# Motherboard.net
KiCad netlist of a schematic drawn in EAGLE
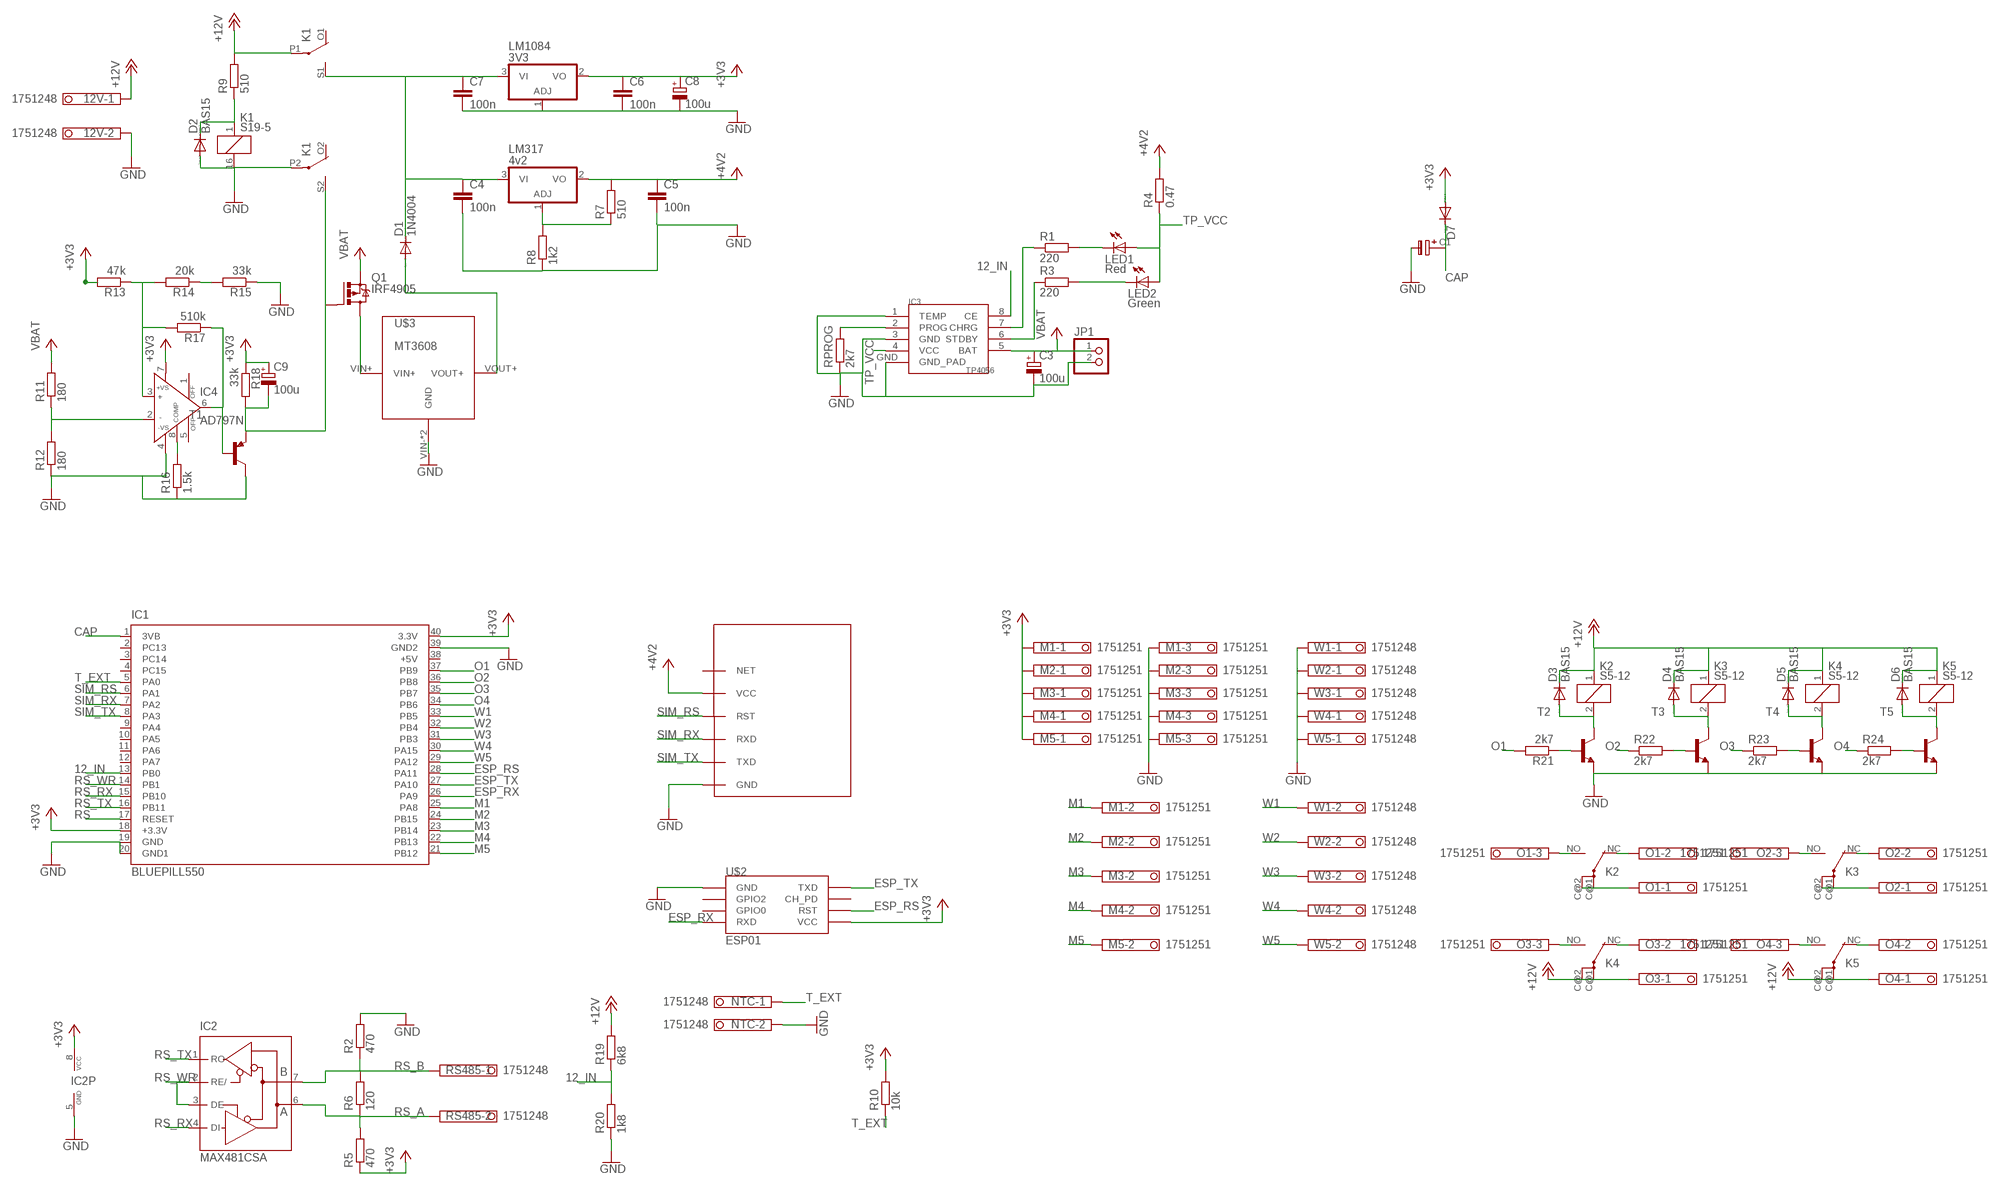
[diagram p0: schematic, sheet 1]

(export (version "E")
  (design (tool "Eeschema 10.0.6"))
  (components
    (comp (ref "12V")
      (value "1751248")
      (footprint "eagle-import:1751248")
      (libsource (lib "eagle-import") (part "1751248"))
    )
    (comp (ref "C1")
      (value "CAP-13,5")
      (footprint "eagle-import:PAC-G-1")
      (libsource (lib "eagle-import") (part "CAP-13,5"))
    )
    (comp (ref "C3")
      (value "100u")
      (footprint "eagle-import:E2,5-6E")
      (libsource (lib "eagle-import") (part "CPOL-EUE2,5-6E"))
    )
    (comp (ref "C4")
      (value "100n")
      (footprint "eagle-import:C2012")
      (libsource (lib "eagle-import") (part "C-EUC2012"))
    )
    (comp (ref "C5")
      (value "100n")
      (footprint "eagle-import:C2012")
      (libsource (lib "eagle-import") (part "C-EUC2012"))
    )
    (comp (ref "C6")
      (value "100n")
      (footprint "eagle-import:C2012")
      (libsource (lib "eagle-import") (part "C-EUC2012"))
    )
    (comp (ref "C7")
      (value "100n")
      (footprint "eagle-import:C2012")
      (libsource (lib "eagle-import") (part "C-EUC2012"))
    )
    (comp (ref "C8")
      (value "100u")
      (footprint "eagle-import:E2,5-6E")
      (libsource (lib "eagle-import") (part "CPOL-EUE2,5-6E"))
    )
    (comp (ref "C9")
      (value "100u")
      (footprint "eagle-import:E2,5-6E")
      (libsource (lib "eagle-import") (part "CPOL-EUE2,5-6E"))
    )
    (comp (ref "D1")
      (value "1N4004")
      (footprint "eagle-import:DO41-10")
      (libsource (lib "eagle-import") (part "1N4004"))
    )
    (comp (ref "D2")
      (value "BAS15")
      (footprint "eagle-import:DO34-7")
      (libsource (lib "eagle-import") (part "BAS15"))
    )
    (comp (ref "D3")
      (value "BAS15")
      (footprint "eagle-import:DO34-7")
      (libsource (lib "eagle-import") (part "BAS15"))
    )
    (comp (ref "D4")
      (value "BAS15")
      (footprint "eagle-import:DO34-7")
      (libsource (lib "eagle-import") (part "BAS15"))
    )
    (comp (ref "D5")
      (value "BAS15")
      (footprint "eagle-import:DO34-7")
      (libsource (lib "eagle-import") (part "BAS15"))
    )
    (comp (ref "D6")
      (value "BAS15")
      (footprint "eagle-import:DO34-7")
      (libsource (lib "eagle-import") (part "BAS15"))
    )
    (comp (ref "D7")
      (value "BAS15")
      (footprint "eagle-import:DO34-7")
      (libsource (lib "eagle-import") (part "BAS15"))
    )
    (comp (ref "IC1")
      (value "BLUEPILL550")
      (footprint "eagle-import:DIL40")
      (fields (field (name "MF") "BluePill"))
      (libsource (lib "eagle-import") (part "BLUEPILL550"))
    )
    (comp (ref "IC2")
      (value "MAX481CSA")
      (footprint "eagle-import:SO08")
      (fields (field (name "MF") "MAXIM"))
      (libsource (lib "eagle-import") (part "MAX481CSA"))
    )
    (comp (ref "IC3")
      (value "TP4056")
      (footprint "eagle-import:SOP-8")
      (libsource (lib "eagle-import") (part "TP4056"))
    )
    (comp (ref "IC4")
      (value "AD797N")
      (footprint "eagle-import:DIL08")
      (fields (field (name "MF") "ALTERA CORPORATION") (field (name "MPN") "AD797ANZ"))
      (libsource (lib "eagle-import") (part "AD797N"))
    )
    (comp (ref "JP1")
      (value "PINHD-1X2")
      (footprint "eagle-import:1X02")
      (libsource (lib "eagle-import") (part "PINHD-1X2"))
    )
    (comp (ref "K1")
      (value "S19-5")
      (footprint "eagle-import:351")
      (libsource (lib "eagle-import") (part "351"))
    )
    (comp (ref "K2")
      (value "S5-12")
      (footprint "eagle-import:HY")
      (fields (field (name "MF") "AROMAT/ MATSUSHITA") (field (name "MPN") "HY1-5V"))
      (libsource (lib "eagle-import") (part "HY1-5V"))
    )
    (comp (ref "K3")
      (value "S5-12")
      (footprint "eagle-import:HY")
      (fields (field (name "MF") "AROMAT/ MATSUSHITA") (field (name "MPN") "HY1-5V"))
      (libsource (lib "eagle-import") (part "HY1-5V"))
    )
    (comp (ref "K4")
      (value "S5-12")
      (footprint "eagle-import:HY")
      (fields (field (name "MF") "AROMAT/ MATSUSHITA") (field (name "MPN") "HY1-5V"))
      (libsource (lib "eagle-import") (part "HY1-5V"))
    )
    (comp (ref "K5")
      (value "S5-12")
      (footprint "eagle-import:HY")
      (fields (field (name "MF") "AROMAT/ MATSUSHITA") (field (name "MPN") "HY1-5V"))
      (libsource (lib "eagle-import") (part "HY1-5V"))
    )
    (comp (ref "LED1")
      (value "Red")
      (footprint "eagle-import:CHIP-LED0805")
      (libsource (lib "eagle-import") (part "LEDCHIP-LED0805"))
    )
    (comp (ref "LED2")
      (value "Green")
      (footprint "eagle-import:CHIP-LED0805")
      (libsource (lib "eagle-import") (part "LEDCHIP-LED0805"))
    )
    (comp (ref "LM317")
      (value "4v2")
      (footprint "eagle-import:TO220H")
      (libsource (lib "eagle-import") (part "317T"))
    )
    (comp (ref "LM1084")
      (value "3V3")
      (footprint "eagle-import:TO220H")
      (libsource (lib "eagle-import") (part "317T"))
    )
    (comp (ref "M1")
      (value "1751251")
      (footprint "eagle-import:1751251")
      (libsource (lib "eagle-import") (part "1751251"))
    )
    (comp (ref "M2")
      (value "1751251")
      (footprint "eagle-import:1751251")
      (libsource (lib "eagle-import") (part "1751251"))
    )
    (comp (ref "M3")
      (value "1751251")
      (footprint "eagle-import:1751251")
      (libsource (lib "eagle-import") (part "1751251"))
    )
    (comp (ref "M4")
      (value "1751251")
      (footprint "eagle-import:1751251")
      (libsource (lib "eagle-import") (part "1751251"))
    )
    (comp (ref "M5")
      (value "1751251")
      (footprint "eagle-import:1751251")
      (libsource (lib "eagle-import") (part "1751251"))
    )
    (comp (ref "NTC")
      (value "1751248")
      (footprint "eagle-import:1751248")
      (libsource (lib "eagle-import") (part "1751248"))
    )
    (comp (ref "O1")
      (value "1751251")
      (footprint "eagle-import:1751251")
      (libsource (lib "eagle-import") (part "1751251"))
    )
    (comp (ref "O2")
      (value "1751251")
      (footprint "eagle-import:1751251")
      (libsource (lib "eagle-import") (part "1751251"))
    )
    (comp (ref "O3")
      (value "1751251")
      (footprint "eagle-import:1751251")
      (libsource (lib "eagle-import") (part "1751251"))
    )
    (comp (ref "O4")
      (value "1751251")
      (footprint "eagle-import:1751251")
      (libsource (lib "eagle-import") (part "1751251"))
    )
    (comp (ref "Q1")
      (value "IRF4905")
      (footprint "eagle-import:TO220BH")
      (libsource (lib "eagle-import") (part "IRF4905"))
    )
    (comp (ref "R1")
      (value "220")
      (footprint "eagle-import:R0805")
      (libsource (lib "eagle-import") (part "resistor_R-EU_R0805"))
    )
    (comp (ref "R2")
      (value "470")
      (footprint "eagle-import:0204_5")
      (libsource (lib "eagle-import") (part "resistor_R-EU_0204/5"))
    )
    (comp (ref "R3")
      (value "220")
      (footprint "eagle-import:R0805")
      (libsource (lib "eagle-import") (part "resistor_R-EU_R0805"))
    )
    (comp (ref "R4")
      (value "0.47")
      (footprint "eagle-import:0207_12")
      (libsource (lib "eagle-import") (part "resistor_R-EU_0207/12"))
    )
    (comp (ref "R5")
      (value "470")
      (footprint "eagle-import:0204_5")
      (libsource (lib "eagle-import") (part "resistor_R-EU_0204/5"))
    )
    (comp (ref "R6")
      (value "120")
      (footprint "eagle-import:0204_7")
      (libsource (lib "eagle-import") (part "resistor_R-EU_0204/7"))
    )
    (comp (ref "R7")
      (value "510")
      (footprint "eagle-import:0204_7")
      (libsource (lib "eagle-import") (part "resistor_R-EU_0204/7"))
    )
    (comp (ref "R8")
      (value "1k2")
      (footprint "eagle-import:0204_7")
      (libsource (lib "eagle-import") (part "resistor_R-EU_0204/7"))
    )
    (comp (ref "R9")
      (value "510")
      (footprint "eagle-import:0204_7")
      (libsource (lib "eagle-import") (part "resistor_R-EU_0204/7"))
    )
    (comp (ref "R10")
      (value "10k")
      (footprint "eagle-import:0204_5")
      (libsource (lib "eagle-import") (part "R-EU_0204/5"))
    )
    (comp (ref "R11")
      (value "180")
      (footprint "eagle-import:0204_7")
      (libsource (lib "eagle-import") (part "resistor_R-EU_0204/7"))
    )
    (comp (ref "R12")
      (value "180")
      (footprint "eagle-import:0204_7")
      (libsource (lib "eagle-import") (part "resistor_R-EU_0204/7"))
    )
    (comp (ref "R13")
      (value "47k")
      (footprint "eagle-import:0204_7")
      (libsource (lib "eagle-import") (part "resistor_R-EU_0204/7"))
    )
    (comp (ref "R14")
      (value "20k")
      (footprint "eagle-import:0204_7")
      (libsource (lib "eagle-import") (part "resistor_R-EU_0204/7"))
    )
    (comp (ref "R15")
      (value "33k")
      (footprint "eagle-import:0204_7")
      (libsource (lib "eagle-import") (part "resistor_R-EU_0204/7"))
    )
    (comp (ref "R16")
      (value "1.5k")
      (footprint "eagle-import:0204_7")
      (libsource (lib "eagle-import") (part "resistor_R-EU_0204/7"))
    )
    (comp (ref "R17")
      (value "510k")
      (footprint "eagle-import:0204_7")
      (libsource (lib "eagle-import") (part "resistor_R-EU_0204/7"))
    )
    (comp (ref "R18")
      (value "33k")
      (footprint "eagle-import:0204_7")
      (libsource (lib "eagle-import") (part "resistor_R-EU_0204/7"))
    )
    (comp (ref "R19")
      (value "6k8")
      (footprint "eagle-import:0204_5")
      (libsource (lib "eagle-import") (part "R-EU_0204/5"))
    )
    (comp (ref "R20")
      (value "1k8")
      (footprint "eagle-import:0204_5")
      (libsource (lib "eagle-import") (part "R-EU_0204/5"))
    )
    (comp (ref "R21")
      (value "2k7")
      (footprint "eagle-import:0204_7")
      (libsource (lib "eagle-import") (part "resistor_R-EU_0204/7"))
    )
    (comp (ref "R22")
      (value "2k7")
      (footprint "eagle-import:0204_7")
      (libsource (lib "eagle-import") (part "resistor_R-EU_0204/7"))
    )
    (comp (ref "R23")
      (value "2k7")
      (footprint "eagle-import:0204_7")
      (libsource (lib "eagle-import") (part "resistor_R-EU_0204/7"))
    )
    (comp (ref "R24")
      (value "2k7")
      (footprint "eagle-import:0204_7")
      (libsource (lib "eagle-import") (part "resistor_R-EU_0204/7"))
    )
    (comp (ref "RPROG")
      (value "2k7")
      (footprint "eagle-import:0204_7")
      (libsource (lib "eagle-import") (part "resistor_R-EU_0204/7"))
    )
    (comp (ref "RS485")
      (value "1751248")
      (footprint "eagle-import:1751248")
      (libsource (lib "eagle-import") (part "1751248"))
    )
    (comp (ref "T1")
      (value "BC327-40-PNP-TO92-EBC")
      (footprint "eagle-import:TO92-EBC")
      (libsource (lib "eagle-import") (part "-PNP-TO92-EBCBC327-40"))
    )
    (comp (ref "T2")
      (value "-NPN-TO92-ECB")
      (footprint "eagle-import:TO92-ECB")
      (libsource (lib "eagle-import") (part "-NPN-TO92-ECB"))
    )
    (comp (ref "T3")
      (value "-NPN-TO92-ECB")
      (footprint "eagle-import:TO92-ECB")
      (libsource (lib "eagle-import") (part "-NPN-TO92-ECB"))
    )
    (comp (ref "T4")
      (value "-NPN-TO92-ECB")
      (footprint "eagle-import:TO92-ECB")
      (libsource (lib "eagle-import") (part "-NPN-TO92-ECB"))
    )
    (comp (ref "T5")
      (value "-NPN-TO92-ECB")
      (footprint "eagle-import:TO92-ECB")
      (libsource (lib "eagle-import") (part "-NPN-TO92-ECB"))
    )
    (comp (ref "U$1")
      (value "SIM800L")
      (footprint "eagle-import:SIM-CORE")
      (libsource (lib "eagle-import") (part "SIM800L"))
    )
    (comp (ref "U$2")
      (value "ESP01")
      (footprint "eagle-import:ESP01")
      (libsource (lib "eagle-import") (part "ESP01"))
    )
    (comp (ref "U$3")
      (value "MT3608")
      (footprint "eagle-import:MT3608")
      (libsource (lib "eagle-import") (part "MT3608"))
    )
    (comp (ref "W1")
      (value "1751248")
      (footprint "eagle-import:1751248")
      (libsource (lib "eagle-import") (part "1751248"))
    )
    (comp (ref "W2")
      (value "1751248")
      (footprint "eagle-import:1751248")
      (libsource (lib "eagle-import") (part "1751248"))
    )
    (comp (ref "W3")
      (value "1751248")
      (footprint "eagle-import:1751248")
      (libsource (lib "eagle-import") (part "1751248"))
    )
    (comp (ref "W4")
      (value "1751248")
      (footprint "eagle-import:1751248")
      (libsource (lib "eagle-import") (part "1751248"))
    )
    (comp (ref "W5")
      (value "1751248")
      (footprint "eagle-import:1751248")
      (libsource (lib "eagle-import") (part "1751248"))
    )
  )
  (nets
    (net (code "1") (name "+3V3") (class "Default")
      (node (ref "C6") (pin "1") (pinfunction "1_1") (pintype "passive"))
      (node (ref "C8") (pin "+") (pinfunction "+_+") (pintype "passive"))
      (node (ref "C9") (pin "+") (pinfunction "+_+") (pintype "passive"))
      (node (ref "D7") (pin "A") (pinfunction "A_A") (pintype "passive"))
      (node (ref "IC1") (pin "18") (pinfunction "+3.3V_18") (pintype "bidirectional"))
      (node (ref "IC1") (pin "40") (pinfunction "3.3V_40") (pintype "bidirectional"))
      (node (ref "IC2") (pin "8") (pinfunction "VCC_8") (pintype "power_in"))
      (node (ref "IC4") (pin "7") (pinfunction "+VS_7") (pintype "input"))
      (node (ref "LM1084") (pin "2") (pinfunction "VO_2") (pintype "passive"))
      (node (ref "M1") (pin "1") (pinfunction "K_1") (pintype "passive"))
      (node (ref "M2") (pin "1") (pinfunction "K_1") (pintype "passive"))
      (node (ref "M3") (pin "1") (pinfunction "K_1") (pintype "passive"))
      (node (ref "M4") (pin "1") (pinfunction "K_1") (pintype "passive"))
      (node (ref "M5") (pin "1") (pinfunction "K_1") (pintype "passive"))
      (node (ref "R10") (pin "2") (pinfunction "2_2") (pintype "passive"))
      (node (ref "R13") (pin "2") (pinfunction "2_2") (pintype "passive"))
      (node (ref "R18") (pin "1") (pinfunction "1_1") (pintype "passive"))
      (node (ref "R5") (pin "1") (pinfunction "1_1") (pintype "passive"))
      (node (ref "U$2") (pin "VCC") (pinfunction "VCC_VCC") (pintype "bidirectional"))
    )
    (net (code "2") (name "+4V2") (class "Default")
      (node (ref "C5") (pin "1") (pinfunction "1_1") (pintype "passive"))
      (node (ref "LM317") (pin "2") (pinfunction "VO_2") (pintype "passive"))
      (node (ref "R4") (pin "2") (pinfunction "2_2") (pintype "passive"))
      (node (ref "R7") (pin "2") (pinfunction "2_2") (pintype "passive"))
      (node (ref "U$1") (pin "VCC") (pinfunction "VCC_VCC") (pintype "bidirectional"))
    )
    (net (code "3") (name "+12V") (class "Default")
      (node (ref "12V") (pin "1") (pinfunction "K_1") (pintype "passive"))
      (node (ref "D3") (pin "C") (pinfunction "C_C") (pintype "passive"))
      (node (ref "D4") (pin "C") (pinfunction "C_C") (pintype "passive"))
      (node (ref "D5") (pin "C") (pinfunction "C_C") (pintype "passive"))
      (node (ref "D6") (pin "C") (pinfunction "C_C") (pintype "passive"))
      (node (ref "K1") (pin "P1") (pinfunction "P_P1") (pintype "passive"))
      (node (ref "K2") (pin "1") (pinfunction "1_1") (pintype "passive"))
      (node (ref "K3") (pin "1") (pinfunction "1_1") (pintype "passive"))
      (node (ref "K4") (pin "1") (pinfunction "1_1") (pintype "passive"))
      (node (ref "K4") (pin "C@1") (pinfunction "P_C@1") (pintype "passive"))
      (node (ref "K4") (pin "C@2") (pinfunction "P_C@2") (pintype "passive"))
      (node (ref "K5") (pin "1") (pinfunction "1_1") (pintype "passive"))
      (node (ref "K5") (pin "C@1") (pinfunction "P_C@1") (pintype "passive"))
      (node (ref "K5") (pin "C@2") (pinfunction "P_C@2") (pintype "passive"))
      (node (ref "O3") (pin "1") (pinfunction "K_1") (pintype "passive"))
      (node (ref "O4") (pin "1") (pinfunction "K_1") (pintype "passive"))
      (node (ref "R19") (pin "2") (pinfunction "2_2") (pintype "passive"))
      (node (ref "R9") (pin "2") (pinfunction "2_2") (pintype "passive"))
    )
    (net (code "4") (name "/12_IN") (class "Default")
      (node (ref "IC1") (pin "13") (pinfunction "PB0_13") (pintype "input"))
      (node (ref "IC3") (pin "8") (pinfunction "CE_8") (pintype "bidirectional"))
      (node (ref "R19") (pin "1") (pinfunction "1_1") (pintype "passive"))
      (node (ref "R20") (pin "2") (pinfunction "2_2") (pintype "passive"))
    )
    (net (code "5") (name "/CAP") (class "Default")
      (node (ref "C1") (pin "+") (pinfunction "+_+") (pintype "passive"))
      (node (ref "D7") (pin "C") (pinfunction "C_C") (pintype "passive"))
      (node (ref "IC1") (pin "1") (pinfunction "3VB_1") (pintype "input"))
    )
    (net (code "6") (name "/ESP_RS") (class "Default")
      (node (ref "IC1") (pin "28") (pinfunction "PA11_28") (pintype "bidirectional"))
      (node (ref "U$2") (pin "RST") (pinfunction "RST_RST") (pintype "bidirectional"))
    )
    (net (code "7") (name "/ESP_RX") (class "Default")
      (node (ref "IC1") (pin "26") (pinfunction "PA9_26") (pintype "bidirectional"))
      (node (ref "U$2") (pin "RX") (pinfunction "RXD_RX") (pintype "bidirectional"))
    )
    (net (code "8") (name "/ESP_TX") (class "Default")
      (node (ref "IC1") (pin "27") (pinfunction "PA10_27") (pintype "bidirectional"))
      (node (ref "U$2") (pin "TX") (pinfunction "TXD_TX") (pintype "bidirectional"))
    )
    (net (code "9") (name "/M1") (class "Default")
      (node (ref "IC1") (pin "25") (pinfunction "PA8_25") (pintype "bidirectional"))
      (node (ref "M1") (pin "2") (pinfunction "K_2") (pintype "passive"))
    )
    (net (code "10") (name "/M2") (class "Default")
      (node (ref "IC1") (pin "24") (pinfunction "PB15_24") (pintype "bidirectional"))
      (node (ref "M2") (pin "2") (pinfunction "K_2") (pintype "passive"))
    )
    (net (code "11") (name "/M3") (class "Default")
      (node (ref "IC1") (pin "23") (pinfunction "PB14_23") (pintype "bidirectional"))
      (node (ref "M3") (pin "2") (pinfunction "K_2") (pintype "passive"))
    )
    (net (code "12") (name "/M4") (class "Default")
      (node (ref "IC1") (pin "22") (pinfunction "PB13_22") (pintype "bidirectional"))
      (node (ref "M4") (pin "2") (pinfunction "K_2") (pintype "passive"))
    )
    (net (code "13") (name "/M5") (class "Default")
      (node (ref "IC1") (pin "21") (pinfunction "PB12_21") (pintype "bidirectional"))
      (node (ref "M5") (pin "2") (pinfunction "K_2") (pintype "passive"))
    )
    (net (code "14") (name "/O1") (class "Default")
      (node (ref "IC1") (pin "37") (pinfunction "PB9_37") (pintype "bidirectional"))
      (node (ref "R21") (pin "2") (pinfunction "2_2") (pintype "passive"))
    )
    (net (code "15") (name "/O2") (class "Default")
      (node (ref "IC1") (pin "36") (pinfunction "PB8_36") (pintype "bidirectional"))
      (node (ref "R22") (pin "1") (pinfunction "1_1") (pintype "passive"))
    )
    (net (code "16") (name "/O3") (class "Default")
      (node (ref "IC1") (pin "35") (pinfunction "PB7_35") (pintype "bidirectional"))
      (node (ref "R23") (pin "1") (pinfunction "1_1") (pintype "passive"))
    )
    (net (code "17") (name "/O4") (class "Default")
      (node (ref "IC1") (pin "34") (pinfunction "PB6_34") (pintype "bidirectional"))
      (node (ref "R24") (pin "1") (pinfunction "1_1") (pintype "passive"))
    )
    (net (code "18") (name "/PA6") (class "Default")
      (node (ref "IC1") (pin "11") (pinfunction "PA6_11") (pintype "power_in"))
    )
    (net (code "19") (name "/PA7") (class "Default")
      (node (ref "IC1") (pin "12") (pinfunction "PA7_12") (pintype "power_in"))
    )
    (net (code "20") (name "/RS") (class "Default")
      (node (ref "IC1") (pin "17") (pinfunction "RESET_17") (pintype "bidirectional"))
    )
    (net (code "21") (name "/RS_A") (class "Default")
      (node (ref "IC2") (pin "6") (pinfunction "A_6") (pintype "passive"))
      (node (ref "R5") (pin "2") (pinfunction "2_2") (pintype "passive"))
      (node (ref "R6") (pin "1") (pinfunction "1_1") (pintype "passive"))
      (node (ref "RS485") (pin "2") (pinfunction "K_2") (pintype "passive"))
    )
    (net (code "22") (name "/RS_B") (class "Default")
      (node (ref "IC2") (pin "7") (pinfunction "B_7") (pintype "passive"))
      (node (ref "R2") (pin "1") (pinfunction "1_1") (pintype "passive"))
      (node (ref "R6") (pin "2") (pinfunction "2_2") (pintype "passive"))
      (node (ref "RS485") (pin "1") (pinfunction "K_1") (pintype "passive"))
    )
    (net (code "23") (name "/RS_RX") (class "Default")
      (node (ref "IC1") (pin "15") (pinfunction "PB10_15") (pintype "bidirectional"))
      (node (ref "IC2") (pin "4") (pinfunction "DI_4") (pintype "input"))
    )
    (net (code "24") (name "/RS_TX") (class "Default")
      (node (ref "IC1") (pin "16") (pinfunction "PB11_16") (pintype "bidirectional"))
      (node (ref "IC2") (pin "1") (pinfunction "RO_1") (pintype "output"))
    )
    (net (code "25") (name "/RS_WR") (class "Default")
      (node (ref "IC1") (pin "14") (pinfunction "PB1_14") (pintype "output"))
      (node (ref "IC2") (pin "2") (pinfunction "RE/_2") (pintype "input"))
      (node (ref "IC2") (pin "3") (pinfunction "DE_3") (pintype "input"))
    )
    (net (code "26") (name "/SIM_RS") (class "Default")
      (node (ref "IC1") (pin "6") (pinfunction "PA1_6") (pintype "bidirectional"))
      (node (ref "U$1") (pin "RST") (pinfunction "RST_RST") (pintype "bidirectional"))
    )
    (net (code "27") (name "/SIM_RX") (class "Default")
      (node (ref "IC1") (pin "7") (pinfunction "PA2_7") (pintype "bidirectional"))
      (node (ref "U$1") (pin "RXD") (pinfunction "RXD_RXD") (pintype "bidirectional"))
    )
    (net (code "28") (name "/SIM_TX") (class "Default")
      (node (ref "IC1") (pin "8") (pinfunction "PA3_8") (pintype "bidirectional"))
      (node (ref "U$1") (pin "TXD") (pinfunction "TXD_TXD") (pintype "bidirectional"))
    )
    (net (code "29") (name "/TP_VCC") (class "Default")
      (node (ref "IC3") (pin "4") (pinfunction "VCC_4") (pintype "bidirectional"))
      (node (ref "LED1") (pin "A") (pinfunction "A_A") (pintype "passive"))
      (node (ref "LED2") (pin "A") (pinfunction "A_A") (pintype "passive"))
      (node (ref "R4") (pin "1") (pinfunction "1_1") (pintype "passive"))
    )
    (net (code "30") (name "/T_EXT") (class "Default")
      (node (ref "IC1") (pin "5") (pinfunction "PA0_5") (pintype "bidirectional"))
      (node (ref "NTC") (pin "1") (pinfunction "K_1") (pintype "passive"))
      (node (ref "R10") (pin "1") (pinfunction "1_1") (pintype "passive"))
    )
    (net (code "31") (name "/W1") (class "Default")
      (node (ref "IC1") (pin "33") (pinfunction "PB5_33") (pintype "bidirectional"))
      (node (ref "W1") (pin "2") (pinfunction "K_2") (pintype "passive"))
    )
    (net (code "32") (name "/W2") (class "Default")
      (node (ref "IC1") (pin "32") (pinfunction "PB4_32") (pintype "power_in"))
      (node (ref "W2") (pin "2") (pinfunction "K_2") (pintype "passive"))
    )
    (net (code "33") (name "/W3") (class "Default")
      (node (ref "IC1") (pin "31") (pinfunction "PB3_31") (pintype "power_in"))
      (node (ref "W3") (pin "2") (pinfunction "K_2") (pintype "passive"))
    )
    (net (code "34") (name "/W4") (class "Default")
      (node (ref "IC1") (pin "30") (pinfunction "PA15_30") (pintype "bidirectional"))
      (node (ref "W4") (pin "2") (pinfunction "K_2") (pintype "passive"))
    )
    (net (code "35") (name "/W5") (class "Default")
      (node (ref "IC1") (pin "29") (pinfunction "PA12_29") (pintype "bidirectional"))
      (node (ref "W5") (pin "2") (pinfunction "K_2") (pintype "passive"))
    )
    (net (code "36") (name "GND") (class "Default")
      (node (ref "12V") (pin "2") (pinfunction "K_2") (pintype "passive"))
      (node (ref "C1") (pin "-") (pinfunction "-_-") (pintype "passive"))
      (node (ref "C3") (pin "-") (pinfunction "-_-") (pintype "passive"))
      (node (ref "C4") (pin "2") (pinfunction "2_2") (pintype "passive"))
      (node (ref "C5") (pin "2") (pinfunction "2_2") (pintype "passive"))
      (node (ref "C6") (pin "2") (pinfunction "2_2") (pintype "passive"))
      (node (ref "C7") (pin "2") (pinfunction "2_2") (pintype "passive"))
      (node (ref "C8") (pin "-") (pinfunction "-_-") (pintype "passive"))
      (node (ref "D2") (pin "A") (pinfunction "A_A") (pintype "passive"))
      (node (ref "IC1") (pin "19") (pinfunction "GND_19") (pintype "bidirectional"))
      (node (ref "IC1") (pin "20") (pinfunction "GND1_20") (pintype "bidirectional"))
      (node (ref "IC1") (pin "39") (pinfunction "GND2_39") (pintype "bidirectional"))
      (node (ref "IC2") (pin "5") (pinfunction "GND_5") (pintype "power_in"))
      (node (ref "IC3") (pin "1") (pinfunction "TEMP_1") (pintype "bidirectional"))
      (node (ref "IC3") (pin "3") (pinfunction "GND_3") (pintype "bidirectional"))
      (node (ref "IC3") (pin "GND") (pinfunction "GND_PAD_GND") (pintype "bidirectional"))
      (node (ref "IC4") (pin "4") (pinfunction "-VS_4") (pintype "input"))
      (node (ref "JP1") (pin "2") (pinfunction "2_2") (pintype "passive"))
      (node (ref "K1") (pin "16") (pinfunction "2_16") (pintype "passive"))
      (node (ref "K1") (pin "P2") (pinfunction "P_P2") (pintype "passive"))
      (node (ref "LM1084") (pin "1") (pinfunction "ADJ_1") (pintype "input"))
      (node (ref "M1") (pin "3") (pinfunction "K_3") (pintype "passive"))
      (node (ref "M2") (pin "3") (pinfunction "K_3") (pintype "passive"))
      (node (ref "M3") (pin "3") (pinfunction "K_3") (pintype "passive"))
      (node (ref "M4") (pin "3") (pinfunction "K_3") (pintype "passive"))
      (node (ref "M5") (pin "3") (pinfunction "K_3") (pintype "passive"))
      (node (ref "NTC") (pin "2") (pinfunction "K_2") (pintype "passive"))
      (node (ref "R12") (pin "1") (pinfunction "1_1") (pintype "passive"))
      (node (ref "R15") (pin "1") (pinfunction "1_1") (pintype "passive"))
      (node (ref "R16") (pin "1") (pinfunction "1_1") (pintype "passive"))
      (node (ref "R2") (pin "2") (pinfunction "2_2") (pintype "passive"))
      (node (ref "R20") (pin "1") (pinfunction "1_1") (pintype "passive"))
      (node (ref "R8") (pin "1") (pinfunction "1_1") (pintype "passive"))
      (node (ref "RPROG") (pin "1") (pinfunction "1_1") (pintype "passive"))
      (node (ref "T1") (pin "C") (pinfunction "C_C") (pintype "passive"))
      (node (ref "T2") (pin "E") (pinfunction "E_E") (pintype "passive"))
      (node (ref "T3") (pin "E") (pinfunction "E_E") (pintype "passive"))
      (node (ref "T4") (pin "E") (pinfunction "E_E") (pintype "passive"))
      (node (ref "T5") (pin "E") (pinfunction "E_E") (pintype "passive"))
      (node (ref "U$1") (pin "GND") (pinfunction "GND_GND") (pintype "bidirectional"))
      (node (ref "U$2") (pin "GND") (pinfunction "GND_GND") (pintype "bidirectional"))
      (node (ref "U$3") (pin "VIN-") (pinfunction "GND_VIN-") (pintype "power_in"))
      (node (ref "U$3") (pin "VOUT-") (pinfunction "GND_VOUT-") (pintype "power_in"))
      (node (ref "W1") (pin "1") (pinfunction "K_1") (pintype "passive"))
      (node (ref "W2") (pin "1") (pinfunction "K_1") (pintype "passive"))
      (node (ref "W3") (pin "1") (pinfunction "K_1") (pintype "passive"))
      (node (ref "W4") (pin "1") (pinfunction "K_1") (pintype "passive"))
      (node (ref "W5") (pin "1") (pinfunction "K_1") (pintype "passive"))
    )
    (net (code "37") (name "Net-(D1-PadA)") (class "Default")
      (node (ref "D1") (pin "A") (pinfunction "A_A") (pintype "passive"))
      (node (ref "U$3") (pin "VOUT+") (pinfunction "VOUT+_VOUT+") (pintype "power_in"))
    )
    (net (code "38") (name "Net-(D2-PadC)") (class "Default")
      (node (ref "D2") (pin "C") (pinfunction "C_C") (pintype "passive"))
      (node (ref "K1") (pin "1") (pinfunction "1_1") (pintype "passive"))
      (node (ref "R9") (pin "1") (pinfunction "1_1") (pintype "passive"))
    )
    (net (code "39") (name "Net-(D3-PadA)") (class "Default")
      (node (ref "D3") (pin "A") (pinfunction "A_A") (pintype "passive"))
      (node (ref "K2") (pin "2") (pinfunction "2_2") (pintype "passive"))
      (node (ref "T2") (pin "C") (pinfunction "C_C") (pintype "passive"))
    )
    (net (code "40") (name "Net-(D4-PadA)") (class "Default")
      (node (ref "D4") (pin "A") (pinfunction "A_A") (pintype "passive"))
      (node (ref "K3") (pin "2") (pinfunction "2_2") (pintype "passive"))
      (node (ref "T3") (pin "C") (pinfunction "C_C") (pintype "passive"))
    )
    (net (code "41") (name "Net-(D5-PadA)") (class "Default")
      (node (ref "D5") (pin "A") (pinfunction "A_A") (pintype "passive"))
      (node (ref "K4") (pin "2") (pinfunction "2_2") (pintype "passive"))
      (node (ref "T4") (pin "C") (pinfunction "C_C") (pintype "passive"))
    )
    (net (code "42") (name "Net-(D6-PadA)") (class "Default")
      (node (ref "D6") (pin "A") (pinfunction "A_A") (pintype "passive"))
      (node (ref "K5") (pin "2") (pinfunction "2_2") (pintype "passive"))
      (node (ref "T5") (pin "C") (pinfunction "C_C") (pintype "passive"))
    )
    (net (code "43") (name "Net-(IC3-CHRG)") (class "Default")
      (node (ref "IC3") (pin "7") (pinfunction "CHRG_7") (pintype "bidirectional"))
      (node (ref "R1") (pin "1") (pinfunction "1_1") (pintype "passive"))
    )
    (net (code "44") (name "Net-(IC3-PROG)") (class "Default")
      (node (ref "IC3") (pin "2") (pinfunction "PROG_2") (pintype "bidirectional"))
      (node (ref "RPROG") (pin "2") (pinfunction "2_2") (pintype "passive"))
    )
    (net (code "45") (name "Net-(IC3-STDBY)") (class "Default")
      (node (ref "IC3") (pin "6") (pinfunction "STDBY_6") (pintype "bidirectional"))
      (node (ref "R3") (pin "1") (pinfunction "1_1") (pintype "passive"))
    )
    (net (code "46") (name "Net-(IC4-COMP)") (class "Default")
      (node (ref "IC4") (pin "8") (pinfunction "COMP_8") (pintype "passive"))
      (node (ref "R16") (pin "2") (pinfunction "2_2") (pintype "passive"))
    )
    (net (code "47") (name "Net-(IC4-IN+)") (class "Default")
      (node (ref "IC4") (pin "3") (pinfunction "IN+_3") (pintype "input"))
      (node (ref "R13") (pin "1") (pinfunction "1_1") (pintype "passive"))
      (node (ref "R14") (pin "2") (pinfunction "2_2") (pintype "passive"))
      (node (ref "R17") (pin "2") (pinfunction "2_2") (pintype "passive"))
    )
    (net (code "48") (name "Net-(IC4-IN-)") (class "Default")
      (node (ref "IC4") (pin "2") (pinfunction "IN-_2") (pintype "input"))
      (node (ref "R11") (pin "1") (pinfunction "1_1") (pintype "passive"))
      (node (ref "R12") (pin "2") (pinfunction "2_2") (pintype "passive"))
    )
    (net (code "49") (name "Net-(IC4-OUT)") (class "Default")
      (node (ref "IC4") (pin "6") (pinfunction "OUT_6") (pintype "output"))
      (node (ref "R17") (pin "1") (pinfunction "1_1") (pintype "passive"))
      (node (ref "T1") (pin "B") (pinfunction "B_B") (pintype "passive"))
    )
    (net (code "50") (name "Net-(K1B-S)") (class "Default")
      (node (ref "C4") (pin "1") (pinfunction "1_1") (pintype "passive"))
      (node (ref "C7") (pin "1") (pinfunction "1_1") (pintype "passive"))
      (node (ref "D1") (pin "C") (pinfunction "C_C") (pintype "passive"))
      (node (ref "K1") (pin "S1") (pinfunction "S_S1") (pintype "passive"))
      (node (ref "LM1084") (pin "3") (pinfunction "VI_3") (pintype "input"))
      (node (ref "LM317") (pin "3") (pinfunction "VI_3") (pintype "input"))
    )
    (net (code "51") (name "Net-(K1C-S)") (class "Default")
      (node (ref "C9") (pin "-") (pinfunction "-_-") (pintype "passive"))
      (node (ref "K1") (pin "S2") (pinfunction "S_S2") (pintype "passive"))
      (node (ref "Q1") (pin "G") (pinfunction "G_G") (pintype "passive"))
      (node (ref "R18") (pin "2") (pinfunction "2_2") (pintype "passive"))
      (node (ref "T1") (pin "E") (pinfunction "E_E") (pintype "passive"))
    )
    (net (code "52") (name "Net-(K2B-O)") (class "Default")
      (node (ref "K2") (pin "NC") (pinfunction "O_NC") (pintype "passive"))
      (node (ref "O1") (pin "2") (pinfunction "K_2") (pintype "passive"))
    )
    (net (code "53") (name "Net-(K2B-S)") (class "Default")
      (node (ref "K2") (pin "NO") (pinfunction "S_NO") (pintype "passive"))
      (node (ref "O1") (pin "3") (pinfunction "K_3") (pintype "passive"))
    )
    (net (code "54") (name "Net-(K3B-O)") (class "Default")
      (node (ref "K3") (pin "NC") (pinfunction "O_NC") (pintype "passive"))
      (node (ref "O2") (pin "2") (pinfunction "K_2") (pintype "passive"))
    )
    (net (code "55") (name "Net-(K3B-S)") (class "Default")
      (node (ref "K3") (pin "NO") (pinfunction "S_NO") (pintype "passive"))
      (node (ref "O2") (pin "3") (pinfunction "K_3") (pintype "passive"))
    )
    (net (code "56") (name "Net-(K4B-O)") (class "Default")
      (node (ref "K4") (pin "NC") (pinfunction "O_NC") (pintype "passive"))
      (node (ref "O3") (pin "2") (pinfunction "K_2") (pintype "passive"))
    )
    (net (code "57") (name "Net-(K4B-S)") (class "Default")
      (node (ref "K4") (pin "NO") (pinfunction "S_NO") (pintype "passive"))
      (node (ref "O3") (pin "3") (pinfunction "K_3") (pintype "passive"))
    )
    (net (code "58") (name "Net-(K5B-O)") (class "Default")
      (node (ref "K5") (pin "NC") (pinfunction "O_NC") (pintype "passive"))
      (node (ref "O4") (pin "2") (pinfunction "K_2") (pintype "passive"))
    )
    (net (code "59") (name "Net-(K5B-S)") (class "Default")
      (node (ref "K5") (pin "NO") (pinfunction "S_NO") (pintype "passive"))
      (node (ref "O4") (pin "3") (pinfunction "K_3") (pintype "passive"))
    )
    (net (code "60") (name "Net-(LED1-PadC)") (class "Default")
      (node (ref "LED1") (pin "C") (pinfunction "C_C") (pintype "passive"))
      (node (ref "R1") (pin "2") (pinfunction "2_2") (pintype "passive"))
    )
    (net (code "61") (name "Net-(LED2-PadC)") (class "Default")
      (node (ref "LED2") (pin "C") (pinfunction "C_C") (pintype "passive"))
      (node (ref "R3") (pin "2") (pinfunction "2_2") (pintype "passive"))
    )
    (net (code "62") (name "Net-(LM317-ADJ)") (class "Default")
      (node (ref "LM317") (pin "1") (pinfunction "ADJ_1") (pintype "input"))
      (node (ref "R7") (pin "1") (pinfunction "1_1") (pintype "passive"))
      (node (ref "R8") (pin "2") (pinfunction "2_2") (pintype "passive"))
    )
    (net (code "63") (name "Net-(O1A-K)") (class "Default")
      (node (ref "K2") (pin "C@1") (pinfunction "P_C@1") (pintype "passive"))
      (node (ref "K2") (pin "C@2") (pinfunction "P_C@2") (pintype "passive"))
      (node (ref "O1") (pin "1") (pinfunction "K_1") (pintype "passive"))
    )
    (net (code "64") (name "Net-(O2A-K)") (class "Default")
      (node (ref "K3") (pin "C@1") (pinfunction "P_C@1") (pintype "passive"))
      (node (ref "K3") (pin "C@2") (pinfunction "P_C@2") (pintype "passive"))
      (node (ref "O2") (pin "1") (pinfunction "K_1") (pintype "passive"))
    )
    (net (code "65") (name "Net-(Q1-PadD)") (class "Default")
      (node (ref "Q1") (pin "D") (pinfunction "D_D") (pintype "passive"))
      (node (ref "U$3") (pin "VIN+") (pinfunction "VIN+_VIN+") (pintype "power_in"))
    )
    (net (code "66") (name "Net-(R14-Pad1)") (class "Default")
      (node (ref "R14") (pin "1") (pinfunction "1_1") (pintype "passive"))
      (node (ref "R15") (pin "2") (pinfunction "2_2") (pintype "passive"))
    )
    (net (code "67") (name "Net-(R21-Pad1)") (class "Default")
      (node (ref "R21") (pin "1") (pinfunction "1_1") (pintype "passive"))
      (node (ref "T2") (pin "B") (pinfunction "B_B") (pintype "passive"))
    )
    (net (code "68") (name "Net-(R22-Pad2)") (class "Default")
      (node (ref "R22") (pin "2") (pinfunction "2_2") (pintype "passive"))
      (node (ref "T3") (pin "B") (pinfunction "B_B") (pintype "passive"))
    )
    (net (code "69") (name "Net-(R23-Pad2)") (class "Default")
      (node (ref "R23") (pin "2") (pinfunction "2_2") (pintype "passive"))
      (node (ref "T4") (pin "B") (pinfunction "B_B") (pintype "passive"))
    )
    (net (code "70") (name "Net-(R24-Pad2)") (class "Default")
      (node (ref "R24") (pin "2") (pinfunction "2_2") (pintype "passive"))
      (node (ref "T5") (pin "B") (pinfunction "B_B") (pintype "passive"))
    )
    (net (code "71") (name "VBAT") (class "Default")
      (node (ref "C3") (pin "+") (pinfunction "+_+") (pintype "passive"))
      (node (ref "IC3") (pin "5") (pinfunction "BAT_5") (pintype "bidirectional"))
      (node (ref "JP1") (pin "1") (pinfunction "1_1") (pintype "passive"))
      (node (ref "Q1") (pin "S") (pinfunction "S_S") (pintype "passive"))
      (node (ref "R11") (pin "2") (pinfunction "2_2") (pintype "passive"))
    )
    (net (code "72") (name "unconnected-(IC1-+5V-Pad38)") (class "Default")
      (node (ref "IC1") (pin "38") (pinfunction "+5V_38") (pintype "bidirectional"))
    )
    (net (code "73") (name "unconnected-(IC1-PA4-Pad9)") (class "Default")
      (node (ref "IC1") (pin "9") (pinfunction "PA4_9") (pintype "bidirectional"))
    )
    (net (code "74") (name "unconnected-(IC1-PA5-Pad10)") (class "Default")
      (node (ref "IC1") (pin "10") (pinfunction "PA5_10") (pintype "bidirectional"))
    )
    (net (code "75") (name "unconnected-(IC1-PC13-Pad2)") (class "Default")
      (node (ref "IC1") (pin "2") (pinfunction "PC13_2") (pintype "bidirectional"))
    )
    (net (code "76") (name "unconnected-(IC1-PC14-Pad3)") (class "Default")
      (node (ref "IC1") (pin "3") (pinfunction "PC14_3") (pintype "bidirectional"))
    )
    (net (code "77") (name "unconnected-(IC1-PC15-Pad4)") (class "Default")
      (node (ref "IC1") (pin "4") (pinfunction "PC15_4") (pintype "bidirectional"))
    )
    (net (code "78") (name "unconnected-(IC4-OFF-Pad1)") (class "Default")
      (node (ref "IC4") (pin "1") (pinfunction "OFF_1") (pintype "passive"))
    )
    (net (code "79") (name "unconnected-(IC4-OFF-Pad5)") (class "Default")
      (node (ref "IC4") (pin "5") (pinfunction "OFF_5") (pintype "passive"))
    )
    (net (code "80") (name "unconnected-(K1B-O-PadO1)") (class "Default")
      (node (ref "K1") (pin "O1") (pinfunction "O_O1") (pintype "passive"))
    )
    (net (code "81") (name "unconnected-(K1C-O-PadO2)") (class "Default")
      (node (ref "K1") (pin "O2") (pinfunction "O_O2") (pintype "passive"))
    )
    (net (code "82") (name "unconnected-(U$1-PadNET)") (class "Default")
      (node (ref "U$1") (pin "NET") (pinfunction "NET_NET") (pintype "bidirectional"))
    )
    (net (code "83") (name "unconnected-(U$2-PadCH_PD)") (class "Default")
      (node (ref "U$2") (pin "CH_PD") (pinfunction "CH_PD_CH_PD") (pintype "bidirectional"))
    )
    (net (code "84") (name "unconnected-(U$2-PadGPIO0)") (class "Default")
      (node (ref "U$2") (pin "GPIO0") (pinfunction "GPIO0_GPIO0") (pintype "bidirectional"))
    )
    (net (code "85") (name "unconnected-(U$2-PadGPIO2)") (class "Default")
      (node (ref "U$2") (pin "GPIO2") (pinfunction "GPIO2_GPIO2") (pintype "bidirectional"))
    )
  )
)
